# 25-CURRENT_MONITORING_DEVICES.net
KiCad netlist of a schematic drawn in Altium Designer
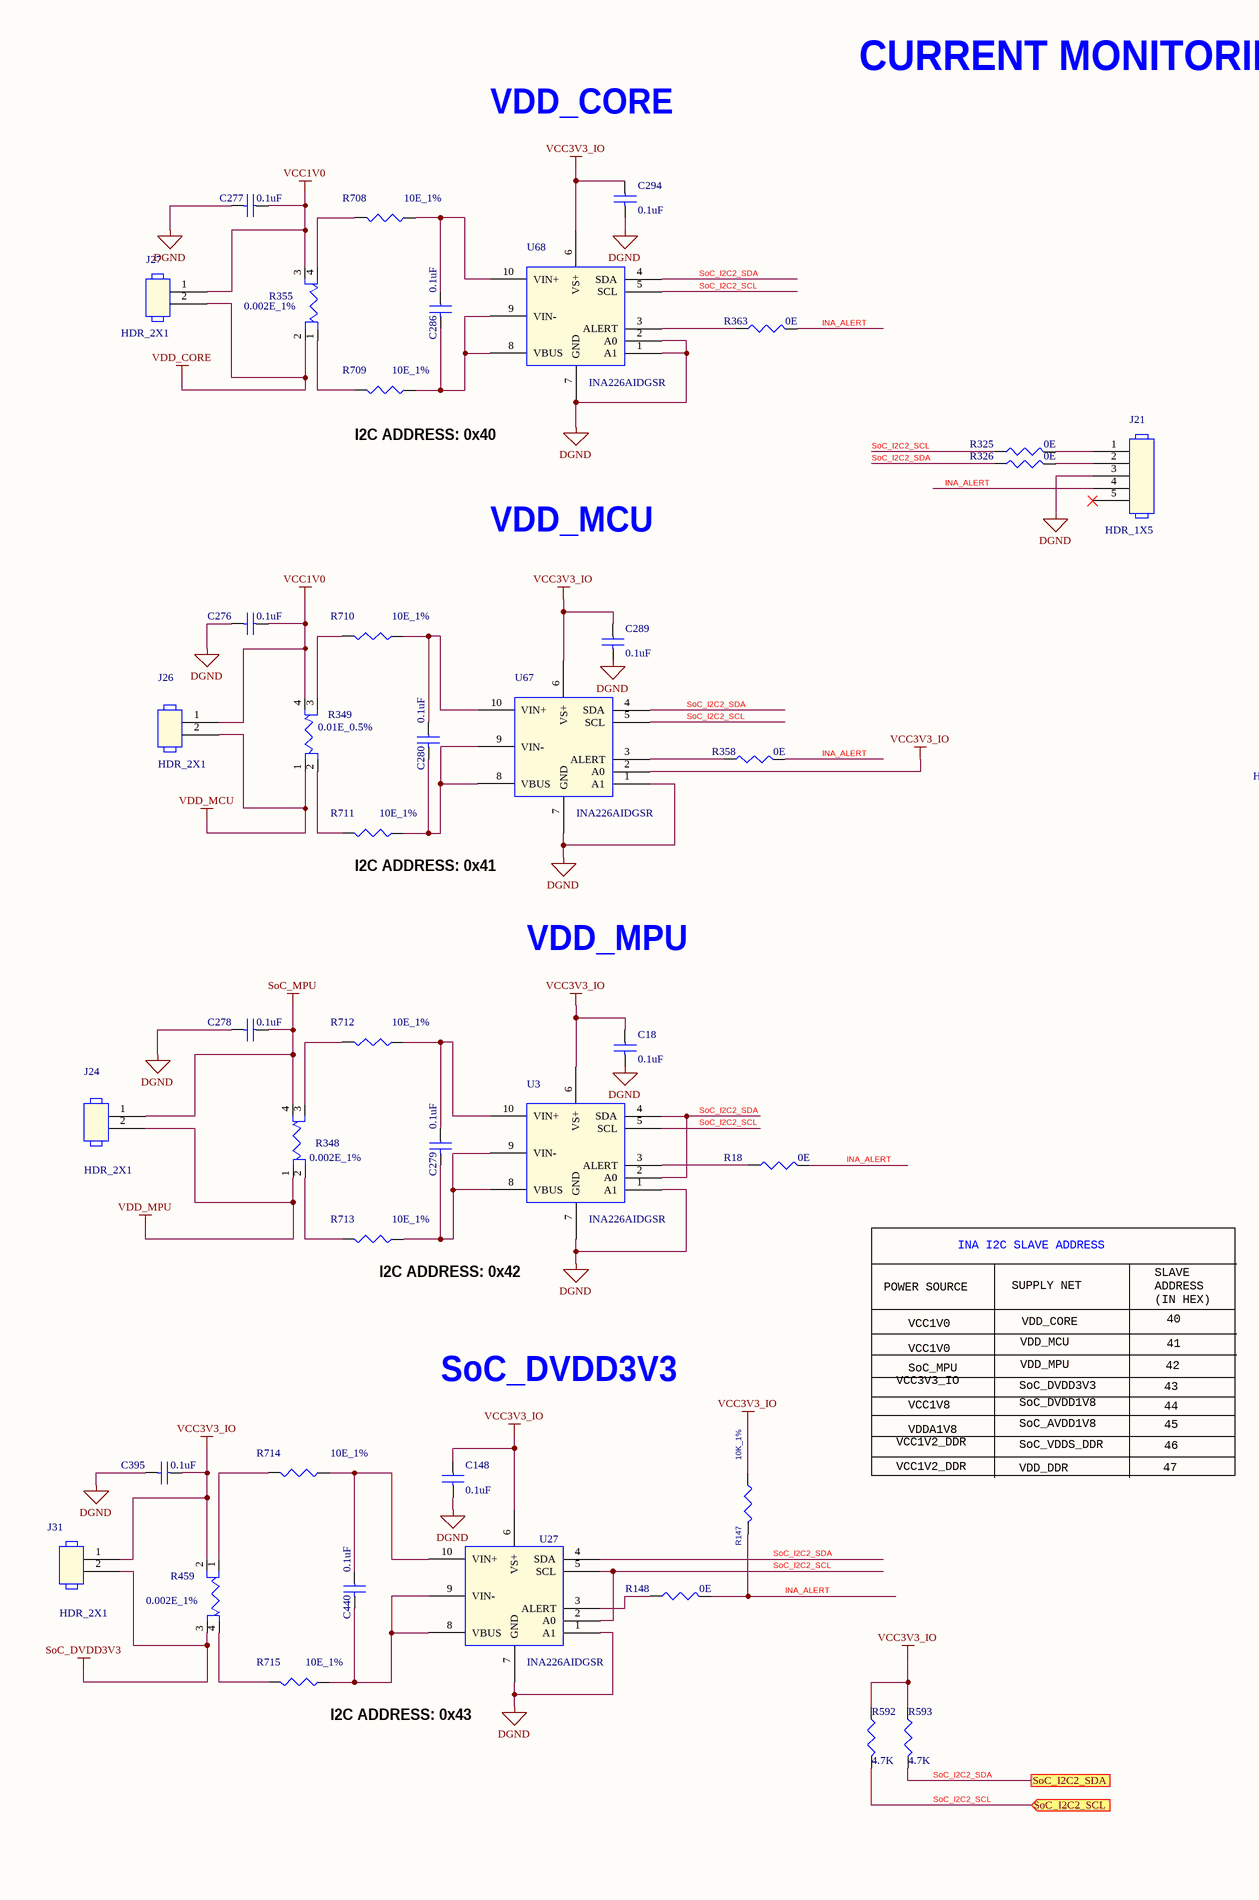
[diagram p0: 25-CURRENT MONITORING DEVICES.SchDoc, left]
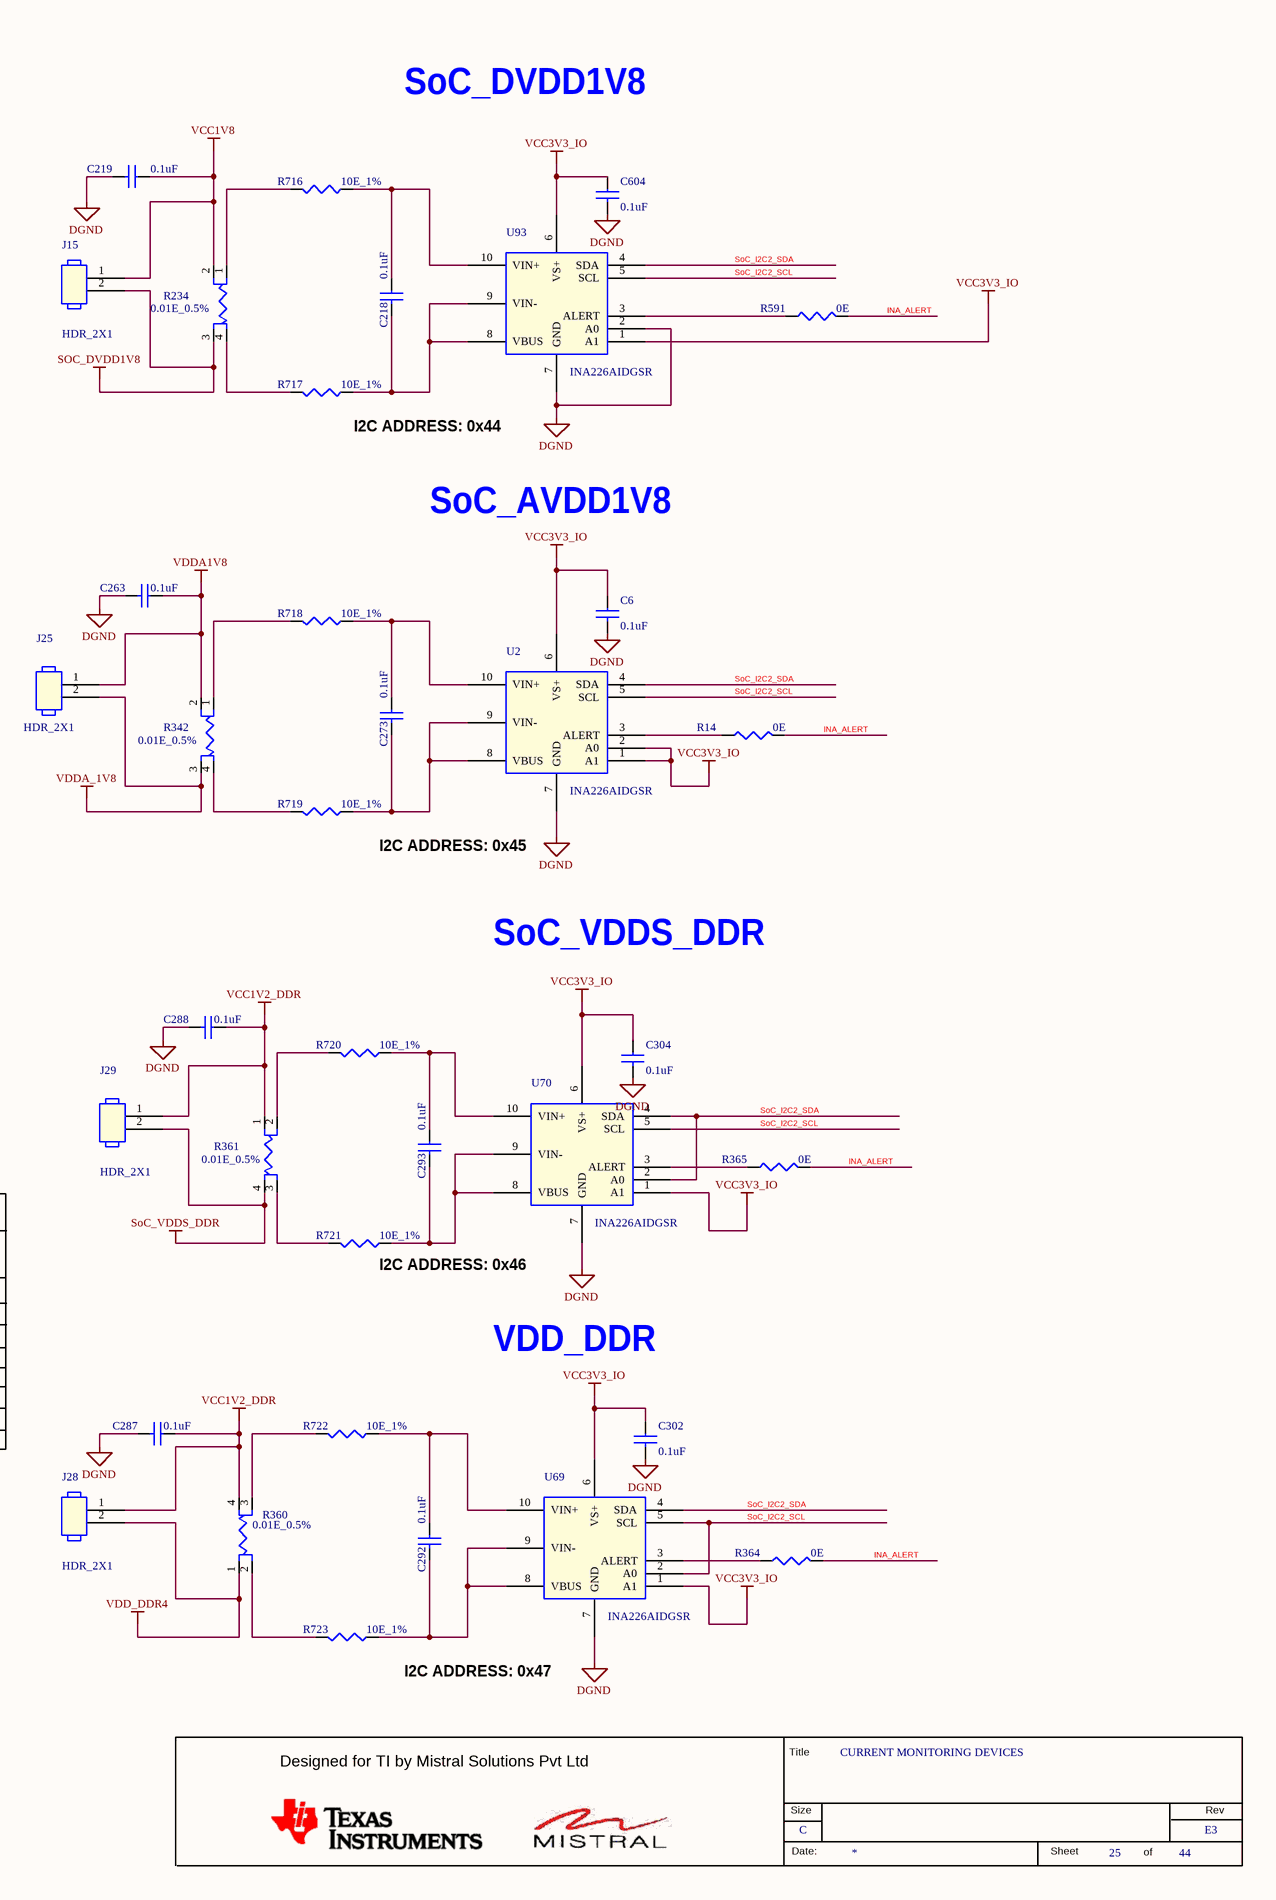
[diagram p1: 25-CURRENT MONITORING DEVICES.SchDoc, right]

(export (version "E")
  (design (tool "Eeschema 10.0.6"))
  (components
    (comp (ref "C6")
      (value "0.1uF")
      (footprint "CAP0201_0-5")
      (description "CAP CERAMIC 0.1uF 16V 10% X5R 0201")
      (fields (field (name "DISTRIBUTOR_PART_NUMBER") "490-16742-1-ND") (field (name "VOLTAGE") "16V"))
      (libsource (lib "*") (part "CAP_Dup5"))
    )
    (comp (ref "C18")
      (value "0.1uF")
      (footprint "CAP0201_0-5")
      (description "CAP CERAMIC 0.1uF 16V 10% X5R 0201")
      (fields
        (field (name "MISTRAL PART NO") "120009030072-R")
        (field (name "MFR_PART_NUMBER") "GRM033R61C104KE84J")
      )
      (libsource (lib "*") (part "CAP_Dup5"))
    )
    (comp (ref "C148")
      (value "0.1uF")
      (footprint "CAP0201_0-5")
      (description "CAP CERAMIC 0.1uF 16V 10% X5R 0201")
      (fields (field (name "DISTRIBUTOR_PART_NUMBER") "490-16742-1-ND") (field (name "VOLTAGE") "16V"))
      (libsource (lib "*") (part "CAP_Dup5"))
    )
    (comp (ref "C218")
      (value "0.1uF")
      (footprint "CAP0201_0-5")
      (description "CAP CERAMIC 0.1uF 16V 10% X5R 0201")
      (fields (field (name "PART_NUMBER") "EC01002") (field (name "MFR_PART_NUMBER") "GRM033R61C104KE84J"))
      (libsource (lib "*") (part "CAP_Dup2"))
    )
    (comp (ref "C219")
      (value "0.1uF")
      (footprint "CAP0201_0-5")
      (description "CAP CERAMIC 0.1uF 16V 10% X5R 0201")
      (fields (field (name "TASER_PART_NUMBER") "EC01002") (field (name "MISTRAL PART NO") "120009030072-R"))
      (libsource (lib "*") (part "CAP_Dup2"))
    )
    (comp (ref "C263")
      (value "0.1uF")
      (footprint "CAP0201_0-5")
      (description "CAP CERAMIC 0.1uF 16V 10% X5R 0201")
      (fields (field (name "PART_NUMBER") "EC01002") (field (name "MFR_PART_NUMBER") "GRM033R61C104KE84J"))
      (libsource (lib "*") (part "CAP_Dup2"))
    )
    (comp (ref "C273")
      (value "0.1uF")
      (footprint "CAP0201_0-5")
      (description "CAP CERAMIC 0.1uF 16V 10% X5R 0201")
      (fields (field (name "TASER_PART_NUMBER") "EC01002") (field (name "MISTRAL PART NO") "120009030072-R"))
      (libsource (lib "*") (part "CAP_Dup2"))
    )
    (comp (ref "C276")
      (value "0.1uF")
      (footprint "CAP0201_0-5")
      (description "CAP CERAMIC 0.1uF 16V 10% X5R 0201")
      (fields (field (name "PART_NUMBER") "EC01002") (field (name "MFR_PART_NUMBER") "GRM033R61C104KE84J"))
      (libsource (lib "*") (part "CAP_Dup2"))
    )
    (comp (ref "C277")
      (value "0.1uF")
      (footprint "CAP0201_0-5")
      (description "CAP CERAMIC 0.1uF 16V 10% X5R 0201")
      (fields (field (name "PART_NUMBER") "EC01002") (field (name "MFR_PART_NUMBER") "GRM033R61C104KE84J"))
      (libsource (lib "*") (part "CAP_Dup2"))
    )
    (comp (ref "C278")
      (value "0.1uF")
      (footprint "CAP0201_0-5")
      (description "CAP CERAMIC 0.1uF 16V 10% X5R 0201")
      (fields (field (name "PART_NUMBER") "EC01002") (field (name "MFR_PART_NUMBER") "GRM033R61C104KE84J"))
      (libsource (lib "*") (part "CAP_Dup2"))
    )
    (comp (ref "C279")
      (value "0.1uF")
      (footprint "CAP0201_0-5")
      (description "CAP CERAMIC 0.1uF 16V 10% X5R 0201")
      (fields (field (name "PART_NUMBER") "EC01002") (field (name "MFR_PART_NUMBER") "GRM033R61C104KE84J"))
      (libsource (lib "*") (part "CAP_Dup2"))
    )
    (comp (ref "C280")
      (value "0.1uF")
      (footprint "CAP0201_0-5")
      (description "CAP CERAMIC 0.1uF 16V 10% X5R 0201")
      (fields (field (name "PART_NUMBER") "EC01002") (field (name "MFR_PART_NUMBER") "GRM033R61C104KE84J"))
      (libsource (lib "*") (part "CAP_Dup2"))
    )
    (comp (ref "C286")
      (value "0.1uF")
      (footprint "CAP0201_0-5")
      (description "CAP CERAMIC 0.1uF 16V 10% X5R 0201")
      (fields (field (name "TASER_PART_NUMBER") "EC01002") (field (name "MISTRAL PART NO") "120009030072-R"))
      (libsource (lib "*") (part "CAP_Dup2"))
    )
    (comp (ref "C287")
      (value "0.1uF")
      (footprint "CAP0201_0-5")
      (description "CAP CERAMIC 0.1uF 16V 10% X5R 0201")
      (fields (field (name "TASER_PART_NUMBER") "EC01002") (field (name "MISTRAL PART NO") "120009030072-R"))
      (libsource (lib "*") (part "CAP_Dup2"))
    )
    (comp (ref "C288")
      (value "0.1uF")
      (footprint "CAP0201_0-5")
      (description "CAP CERAMIC 0.1uF 16V 10% X5R 0201")
      (fields (field (name "PART_NUMBER") "EC01002") (field (name "MFR_PART_NUMBER") "GRM033R61C104KE84J"))
      (libsource (lib "*") (part "CAP_Dup2"))
    )
    (comp (ref "C289")
      (value "0.1uF")
      (footprint "CAP0201_0-5")
      (description "CAP CERAMIC 0.1uF 16V 10% X5R 0201")
      (fields
        (field (name "MISTRAL PART NO") "120009030072-R")
        (field (name "MFR_PART_NUMBER") "GRM033R61C104KE84J")
      )
      (libsource (lib "*") (part "CAP_Dup5"))
    )
    (comp (ref "C292")
      (value "0.1uF")
      (footprint "CAP0201_0-5")
      (description "CAP CERAMIC 0.1uF 16V 10% X5R 0201")
      (fields (field (name "TASER_PART_NUMBER") "EC01002") (field (name "MISTRAL PART NO") "120009030072-R"))
      (libsource (lib "*") (part "CAP_Dup2"))
    )
    (comp (ref "C293")
      (value "0.1uF")
      (footprint "CAP0201_0-5")
      (description "CAP CERAMIC 0.1uF 16V 10% X5R 0201")
      (fields (field (name "TASER_PART_NUMBER") "EC01002") (field (name "MISTRAL PART NO") "120009030072-R"))
      (libsource (lib "*") (part "CAP_Dup2"))
    )
    (comp (ref "C294")
      (value "0.1uF")
      (footprint "CAP0201_0-5")
      (description "CAP CERAMIC 0.1uF 16V 10% X5R 0201")
      (fields
        (field (name "MISTRAL PART NO") "120009030072-R")
        (field (name "MFR_PART_NUMBER") "GRM033R61C104KE84J")
      )
      (libsource (lib "*") (part "CAP_Dup5"))
    )
    (comp (ref "C302")
      (value "0.1uF")
      (footprint "CAP0201_0-5")
      (description "CAP CERAMIC 0.1uF 16V 10% X5R 0201")
      (fields
        (field (name "MISTRAL PART NO") "120009030072-R")
        (field (name "MFR_PART_NUMBER") "GRM033R61C104KE84J")
      )
      (libsource (lib "*") (part "CAP_Dup5"))
    )
    (comp (ref "C304")
      (value "0.1uF")
      (footprint "CAP0201_0-5")
      (description "CAP CERAMIC 0.1uF 16V 10% X5R 0201")
      (fields (field (name "DISTRIBUTOR_PART_NUMBER") "490-16742-1-ND") (field (name "VOLTAGE") "16V"))
      (libsource (lib "*") (part "CAP_Dup5"))
    )
    (comp (ref "C395")
      (value "0.1uF")
      (footprint "CAP0201_0-5")
      (description "CAP CERAMIC 0.1uF 16V 10% X5R 0201")
      (fields (field (name "TASER_PART_NUMBER") "EC01002") (field (name "MISTRAL PART NO") "120009030072-R"))
      (libsource (lib "*") (part "CAP_Dup2"))
    )
    (comp (ref "C440")
      (value "0.1uF")
      (footprint "CAP0201_0-5")
      (description "CAP CERAMIC 0.1uF 16V 10% X5R 0201")
      (fields (field (name "TASER_PART_NUMBER") "EC01002") (field (name "MISTRAL PART NO") "120009030072-R"))
      (libsource (lib "*") (part "CAP_Dup2"))
    )
    (comp (ref "C604")
      (value "0.1uF")
      (footprint "CAP0201_0-5")
      (description "CAP CERAMIC 0.1uF 16V 10% X5R 0201")
      (fields
        (field (name "MISTRAL PART NO") "120009030072-R")
        (field (name "MFR_PART_NUMBER") "GRM033R61C104KE84J")
      )
      (libsource (lib "*") (part "CAP_Dup5"))
    )
    (comp (ref "J15")
      (value "HDR_2X1")
      (footprint "HDR_2X1_100_S_T_10-8")
      (description "CON HDR 2X1 2.54MM PITCH ST TH")
      (fields
        (field (name "DISTRIBUTOR_PART_NUMBER") "WM4000-ND")
        (field (name "MFR_PART_NUMBER") "22-03-2021")
      )
      (libsource (lib "*") (part "HEADER_2X1"))
    )
    (comp (ref "J21")
      (value "HDR_1X5")
      (footprint "HDR_5X1_100_S_T_11-2")
      (description "CON HDR 1X5 2.54MM PITCH ST TH")
      (fields (field (name "VOLTAGE") "NA") (field (name "MISTRAL PART NO") "150009030262-R"))
      (libsource (lib "*") (part "HEADER_5X1"))
    )
    (comp (ref "J24")
      (value "HDR_2X1")
      (footprint "HDR_2X1_100_S_T_10-8")
      (description "CON HDR 2X1 2.54MM PITCH ST TH")
      (fields
        (field (name "DISTRIBUTOR_PART_NUMBER") "WM4000-ND")
        (field (name "MFR_PART_NUMBER") "22-03-2021")
      )
      (libsource (lib "*") (part "HEADER_2X1"))
    )
    (comp (ref "J25")
      (value "HDR_2X1")
      (footprint "HDR_2X1_100_S_T_10-8")
      (description "CON HDR 2X1 2.54MM PITCH ST TH")
      (fields (field (name "VOLTAGE") "NA") (field (name "MISTRAL PART NO") "150009030246-R"))
      (libsource (lib "*") (part "HEADER_2X1"))
    )
    (comp (ref "J26")
      (value "HDR_2X1")
      (footprint "HDR_2X1_100_S_T_10-8")
      (description "CON HDR 2X1 2.54MM PITCH ST TH")
      (fields (field (name "VOLTAGE") "NA") (field (name "MISTRAL PART NO") "150009030246-R"))
      (libsource (lib "*") (part "HEADER_2X1"))
    )
    (comp (ref "J27")
      (value "HDR_2X1")
      (footprint "HDR_2X1_100_S_T_10-8")
      (description "CON HDR 2X1 2.54MM PITCH ST TH")
      (fields (field (name "VOLTAGE") "NA") (field (name "MISTRAL PART NO") "150009030246-R"))
      (libsource (lib "*") (part "HEADER_2X1"))
    )
    (comp (ref "J28")
      (value "HDR_2X1")
      (footprint "HDR_2X1_100_S_T_10-8")
      (description "CON HDR 2X1 2.54MM PITCH ST TH")
      (fields (field (name "VOLTAGE") "NA") (field (name "MISTRAL PART NO") "150009030246-R"))
      (libsource (lib "*") (part "HEADER_2X1"))
    )
    (comp (ref "J29")
      (value "HDR_2X1")
      (footprint "HDR_2X1_100_S_T_10-8")
      (description "CON HDR 2X1 2.54MM PITCH ST TH")
      (fields (field (name "VOLTAGE") "NA") (field (name "MISTRAL PART NO") "150009030246-R"))
      (libsource (lib "*") (part "HEADER_2X1"))
    )
    (comp (ref "J31")
      (value "HDR_2X1")
      (footprint "HDR_2X1_100_S_T_10-8")
      (description "CON HDR 2X1 2.54MM PITCH ST TH")
      (fields
        (field (name "DISTRIBUTOR_PART_NUMBER") "WM4000-ND")
        (field (name "MFR_PART_NUMBER") "22-03-2021")
      )
      (libsource (lib "*") (part "HEADER_2X1"))
    )
    (comp (ref "R14")
      (value "0E")
      (footprint "RES0402_0-5")
      (description "RES 0E 1/16W 0402")
      (fields (field (name "DISTRIBUTOR_PART_NUMBER") "541-0.0JCT-ND") (field (name "VOLTAGE") "NA"))
      (libsource (lib "*") (part "RESISTOR_Dup4"))
    )
    (comp (ref "R18")
      (value "0E")
      (footprint "RES0402_0-5")
      (description "RES 0E 1/16W 0402")
      (fields
        (field (name "MISTRAL PART NO") "110010080019-P")
        (field (name "MFR_PART_NUMBER") "CRCW04020000Z0ED")
      )
      (libsource (lib "*") (part "RESISTOR_Dup4"))
    )
    (comp (ref "R147")
      (value "10K_1%")
      (footprint "RES0402_0-5")
      (description "RES 10K 1/16W 1% 0402")
      (fields
        (field (name "MISTRAL PART NO") "110009030220-P")
        (field (name "MFR_PART_NUMBER") "RC0402FR-0710KL")
      )
      (libsource (lib "*") (part "RESISTOR_Dup2"))
    )
    (comp (ref "R148")
      (value "0E")
      (footprint "RES0402_0-5")
      (description "RES 0E 1/16W 0402")
      (fields
        (field (name "MISTRAL PART NO") "110010080019-P")
        (field (name "MFR_PART_NUMBER") "CRCW04020000Z0ED")
      )
      (libsource (lib "*") (part "RESISTOR_Dup4"))
    )
    (comp (ref "R234")
      (value "0.01E_0.5%")
      (footprint "RES1206-4TERM_0-75")
      (description "RES 0.01E 1/2W 0.5% 4-TERM1206")
      (fields (field (name "DISTRIBUTOR_PART_NUMBER") "LVK12R010DERCT-ND") (field (name "VOLTAGE") "NA"))
      (libsource (lib "*") (part "RESISTOR-4TERM"))
    )
    (comp (ref "R325")
      (value "0E")
      (footprint "RES0402_0-5")
      (description "RES 0E 1/16W 0402")
      (fields
        (field (name "MISTRAL PART NO") "110010080019-P")
        (field (name "MFR_PART_NUMBER") "CRCW04020000Z0ED")
      )
      (libsource (lib "*") (part "RESISTOR_Dup4"))
    )
    (comp (ref "R326")
      (value "0E")
      (footprint "RES0402_0-5")
      (description "RES 0E 1/16W 0402")
      (fields (field (name "DISTRIBUTOR_PART_NUMBER") "541-0.0JCT-ND") (field (name "VOLTAGE") "NA"))
      (libsource (lib "*") (part "RESISTOR_Dup4"))
    )
    (comp (ref "R342")
      (value "0.01E_0.5%")
      (footprint "RES1206-4TERM_0-75")
      (description "RES 0.01E 1/2W 0.5% 4-TERM1206")
      (fields (field (name "DISTRIBUTOR_PART_NUMBER") "LVK12R010DERCT-ND") (field (name "VOLTAGE") "NA"))
      (libsource (lib "*") (part "RESISTOR-4TERM"))
    )
    (comp (ref "R348")
      (value "0.002E_1%")
      (footprint "RES2512-4TERM_0-75")
      (description "RES 0.002E 2W 1% 4-TERM2512")
      (fields (field (name "DISTRIBUTOR_PART_NUMBER") "LVK25R002FERCT-ND") (field (name "VOLTAGE") "NA"))
      (libsource (lib "*") (part "RESISTOR-4TERM"))
    )
    (comp (ref "R349")
      (value "0.01E_0.5%")
      (footprint "RES1206-4TERM_0-75")
      (description "RES 0.01E 1/2W 0.5% 4-TERM1206")
      (fields (field (name "DISTRIBUTOR_PART_NUMBER") "LVK12R010DERCT-ND") (field (name "VOLTAGE") "NA"))
      (libsource (lib "*") (part "RESISTOR-4TERM"))
    )
    (comp (ref "R355")
      (value "0.002E_1%")
      (footprint "RES2512-4TERM_0-75")
      (description "RES 0.002E 2W 1% 4-TERM2512")
      (fields
        (field (name "MISTRAL PART NO") "110017090010-R")
        (field (name "MFR_PART_NUMBER") "LVK25R002FER")
      )
      (libsource (lib "*") (part "RESISTOR-4TERM"))
    )
    (comp (ref "R358")
      (value "0E")
      (footprint "RES0402_0-5")
      (description "RES 0E 1/16W 0402")
      (fields
        (field (name "MISTRAL PART NO") "110010080019-P")
        (field (name "MFR_PART_NUMBER") "CRCW04020000Z0ED")
      )
      (libsource (lib "*") (part "RESISTOR_Dup4"))
    )
    (comp (ref "R360")
      (value "0.01E_0.5%")
      (footprint "RES1206-4TERM_0-75")
      (description "RES 0.01E 1/2W 0.5% 4-TERM1206")
      (fields (field (name "DISTRIBUTOR_PART_NUMBER") "LVK12R010DERCT-ND") (field (name "VOLTAGE") "NA"))
      (libsource (lib "*") (part "RESISTOR-4TERM"))
    )
    (comp (ref "R361")
      (value "0.01E_0.5%")
      (footprint "RES1206-4TERM_0-75")
      (description "RES 0.01E 1/2W 0.5% 4-TERM1206")
      (fields
        (field (name "MISTRAL PART NO") "110017090009-R")
        (field (name "MFR_PART_NUMBER") "LVK12R010DER")
      )
      (libsource (lib "*") (part "RESISTOR-4TERM"))
    )
    (comp (ref "R363")
      (value "0E")
      (footprint "RES0402_0-5")
      (description "RES 0E 1/16W 0402")
      (fields
        (field (name "MISTRAL PART NO") "110010080019-P")
        (field (name "MFR_PART_NUMBER") "CRCW04020000Z0ED")
      )
      (libsource (lib "*") (part "RESISTOR_Dup4"))
    )
    (comp (ref "R364")
      (value "0E")
      (footprint "RES0402_0-5")
      (description "RES 0E 1/16W 0402")
      (fields (field (name "DISTRIBUTOR_PART_NUMBER") "541-0.0JCT-ND") (field (name "VOLTAGE") "NA"))
      (libsource (lib "*") (part "RESISTOR_Dup4"))
    )
    (comp (ref "R365")
      (value "0E")
      (footprint "RES0402_0-5")
      (description "RES 0E 1/16W 0402")
      (fields (field (name "DISTRIBUTOR_PART_NUMBER") "541-0.0JCT-ND") (field (name "VOLTAGE") "NA"))
      (libsource (lib "*") (part "RESISTOR_Dup4"))
    )
    (comp (ref "R459")
      (value "0.002E_1%")
      (footprint "RES2512-4TERM_0-75")
      (description "RES 0.002E 2W 1% 4-TERM2512")
      (fields
        (field (name "MISTRAL PART NO") "110017090010-R")
        (field (name "MFR_PART_NUMBER") "LVK25R002FER")
      )
      (libsource (lib "*") (part "RESISTOR-4TERM"))
    )
    (comp (ref "R591")
      (value "0E")
      (footprint "RES0402_0-5")
      (description "RES 0E 1/16W 0402")
      (fields (field (name "DISTRIBUTOR_PART_NUMBER") "541-0.0JCT-ND") (field (name "VOLTAGE") "NA"))
      (libsource (lib "*") (part "RESISTOR_Dup4"))
    )
    (comp (ref "R592")
      (value "4.7K")
      (footprint "RES0402")
      (description "RES 4.7K 1/16W 5% 0402")
      (fields (field (name "DISTRIBUTOR_PART_NUMBER") "311-4.7KJRCT-ND") (field (name "VOLTAGE") "NA"))
      (libsource (lib "*") (part "RESISTOR_Dup3"))
    )
    (comp (ref "R593")
      (value "4.7K")
      (footprint "RES0402")
      (description "RES 4.7K 1/16W 5% 0402")
      (fields (field (name "DISTRIBUTOR_PART_NUMBER") "311-4.7KJRCT-ND") (field (name "VOLTAGE") "NA"))
      (libsource (lib "*") (part "RESISTOR_Dup3"))
    )
    (comp (ref "R708")
      (value "10E_1%")
      (footprint "RES0402_0-5")
      (description "RES 10E 1/16W 1% 0402")
      (fields
        (field (name "MISTRAL PART NO") "110018020004-R")
        (field (name "MFR_PART_NUMBER") "RC0402FR-0710RL")
      )
      (libsource (lib "*") (part "RESISTOR_Dup5"))
    )
    (comp (ref "R709")
      (value "10E_1%")
      (footprint "RES0402_0-5")
      (description "RES 10E 1/16W 1% 0402")
      (fields (field (name "DISTRIBUTOR_PART_NUMBER") "311-10.0LRCT-ND") (field (name "VOLTAGE") "NA"))
      (libsource (lib "*") (part "RESISTOR_Dup5"))
    )
    (comp (ref "R710")
      (value "10E_1%")
      (footprint "RES0402_0-5")
      (description "RES 10E 1/16W 1% 0402")
      (fields (field (name "DISTRIBUTOR_PART_NUMBER") "311-10.0LRCT-ND") (field (name "VOLTAGE") "NA"))
      (libsource (lib "*") (part "RESISTOR_Dup5"))
    )
    (comp (ref "R711")
      (value "10E_1%")
      (footprint "RES0402_0-5")
      (description "RES 10E 1/16W 1% 0402")
      (fields
        (field (name "MISTRAL PART NO") "110018020004-R")
        (field (name "MFR_PART_NUMBER") "RC0402FR-0710RL")
      )
      (libsource (lib "*") (part "RESISTOR_Dup5"))
    )
    (comp (ref "R712")
      (value "10E_1%")
      (footprint "RES0402_0-5")
      (description "RES 10E 1/16W 1% 0402")
      (fields
        (field (name "MISTRAL PART NO") "110018020004-R")
        (field (name "MFR_PART_NUMBER") "RC0402FR-0710RL")
      )
      (libsource (lib "*") (part "RESISTOR_Dup5"))
    )
    (comp (ref "R713")
      (value "10E_1%")
      (footprint "RES0402_0-5")
      (description "RES 10E 1/16W 1% 0402")
      (fields
        (field (name "MISTRAL PART NO") "110018020004-R")
        (field (name "MFR_PART_NUMBER") "RC0402FR-0710RL")
      )
      (libsource (lib "*") (part "RESISTOR_Dup5"))
    )
    (comp (ref "R714")
      (value "10E_1%")
      (footprint "RES0402_0-5")
      (description "RES 10E 1/16W 1% 0402")
      (fields (field (name "DISTRIBUTOR_PART_NUMBER") "311-10.0LRCT-ND") (field (name "VOLTAGE") "NA"))
      (libsource (lib "*") (part "RESISTOR_Dup5"))
    )
    (comp (ref "R715")
      (value "10E_1%")
      (footprint "RES0402_0-5")
      (description "RES 10E 1/16W 1% 0402")
      (fields (field (name "DISTRIBUTOR_PART_NUMBER") "311-10.0LRCT-ND") (field (name "VOLTAGE") "NA"))
      (libsource (lib "*") (part "RESISTOR_Dup5"))
    )
    (comp (ref "R716")
      (value "10E_1%")
      (footprint "RES0402_0-5")
      (description "RES 10E 1/16W 1% 0402")
      (fields (field (name "DISTRIBUTOR_PART_NUMBER") "311-10.0LRCT-ND") (field (name "VOLTAGE") "NA"))
      (libsource (lib "*") (part "RESISTOR_Dup5"))
    )
    (comp (ref "R717")
      (value "10E_1%")
      (footprint "RES0402_0-5")
      (description "RES 10E 1/16W 1% 0402")
      (fields (field (name "DISTRIBUTOR_PART_NUMBER") "311-10.0LRCT-ND") (field (name "VOLTAGE") "NA"))
      (libsource (lib "*") (part "RESISTOR_Dup5"))
    )
    (comp (ref "R718")
      (value "10E_1%")
      (footprint "RES0402_0-5")
      (description "RES 10E 1/16W 1% 0402")
      (fields (field (name "DISTRIBUTOR_PART_NUMBER") "311-10.0LRCT-ND") (field (name "VOLTAGE") "NA"))
      (libsource (lib "*") (part "RESISTOR_Dup5"))
    )
    (comp (ref "R719")
      (value "10E_1%")
      (footprint "RES0402_0-5")
      (description "RES 10E 1/16W 1% 0402")
      (fields (field (name "DISTRIBUTOR_PART_NUMBER") "311-10.0LRCT-ND") (field (name "VOLTAGE") "NA"))
      (libsource (lib "*") (part "RESISTOR_Dup5"))
    )
    (comp (ref "R720")
      (value "10E_1%")
      (footprint "RES0402_0-5")
      (description "RES 10E 1/16W 1% 0402")
      (fields (field (name "DISTRIBUTOR_PART_NUMBER") "311-10.0LRCT-ND") (field (name "VOLTAGE") "NA"))
      (libsource (lib "*") (part "RESISTOR_Dup5"))
    )
    (comp (ref "R721")
      (value "10E_1%")
      (footprint "RES0402_0-5")
      (description "RES 10E 1/16W 1% 0402")
      (fields (field (name "DISTRIBUTOR_PART_NUMBER") "311-10.0LRCT-ND") (field (name "VOLTAGE") "NA"))
      (libsource (lib "*") (part "RESISTOR_Dup5"))
    )
    (comp (ref "R722")
      (value "10E_1%")
      (footprint "RES0402_0-5")
      (description "RES 10E 1/16W 1% 0402")
      (fields (field (name "DISTRIBUTOR_PART_NUMBER") "311-10.0LRCT-ND") (field (name "VOLTAGE") "NA"))
      (libsource (lib "*") (part "RESISTOR_Dup5"))
    )
    (comp (ref "R723")
      (value "10E_1%")
      (footprint "RES0402_0-5")
      (description "RES 10E 1/16W 1% 0402")
      (fields (field (name "DISTRIBUTOR_PART_NUMBER") "311-10.0LRCT-ND") (field (name "VOLTAGE") "NA"))
      (libsource (lib "*") (part "RESISTOR_Dup5"))
    )
    (comp (ref "U2")
      (value "INA226AIDGSR")
      (footprint "MSOP10_19-68_120X120_1-1")
      (description "IC BI-DIRECTIONAL CURRENT MONITER MSOP10")
      (fields
        (field (name "MISTRAL PART NO") "141011080019-R")
        (field (name "TOLERANCE") "NA")
        (field (name "LIBRARY PATH") "Y~{:}MIS_DATABAS~{E}Librar~{y}ALTIUM_TOO~{L}SCHEMATICS_PART~{S}MS_MISCINTERFACE_Library.schlib")
      )
      (libsource (lib "*") (part "INA226AIDGS_MSOP10"))
    )
    (comp (ref "U3")
      (value "INA226AIDGSR")
      (footprint "MSOP10_19-68_120X120_1-1")
      (description "IC BI-DIRECTIONAL CURRENT MONITER MSOP10")
      (fields
        (field (name "DISTRIBUTOR_PART_NUMBER") "296-29034-1-ND")
        (field (name "VOLTAGE") "NA")
        (field (name "LIBRARY PATH") "Y~{:}MIS_DATABAS~{E}Librar~{y}ALTIUM_TOO~{L}SCHEMATICS_PART~{S}MS_MISCINTERFACE_Library.schlib")
      )
      (libsource (lib "*") (part "INA226AIDGS_MSOP10"))
    )
    (comp (ref "U27")
      (value "INA226AIDGSR")
      (footprint "MSOP10_19-68_120X120_1-1")
      (description "IC BI-DIRECTIONAL CURRENT MONITER MSOP10")
      (fields
        (field (name "DISTRIBUTOR_PART_NUMBER") "296-29034-1-ND")
        (field (name "VOLTAGE") "NA")
        (field (name "LIBRARY PATH") "Y~{:}MIS_DATABAS~{E}Librar~{y}ALTIUM_TOO~{L}SCHEMATICS_PART~{S}MS_MISCINTERFACE_Library.schlib")
      )
      (libsource (lib "*") (part "INA226AIDGS_MSOP10"))
    )
    (comp (ref "U67")
      (value "INA226AIDGSR")
      (footprint "MSOP10_19-68_120X120_1-1")
      (description "IC BI-DIRECTIONAL CURRENT MONITER MSOP10")
      (fields
        (field (name "DISTRIBUTOR_PART_NUMBER") "296-29034-1-ND")
        (field (name "VOLTAGE") "NA")
        (field (name "LIBRARY PATH") "Y~{:}MIS_DATABAS~{E}Librar~{y}ALTIUM_TOO~{L}SCHEMATICS_PART~{S}MS_MISCINTERFACE_Library.schlib")
      )
      (libsource (lib "*") (part "INA226AIDGS_MSOP10"))
    )
    (comp (ref "U68")
      (value "INA226AIDGSR")
      (footprint "MSOP10_19-68_120X120_1-1")
      (description "IC BI-DIRECTIONAL CURRENT MONITER MSOP10")
      (fields
        (field (name "MISTRAL PART NO") "141011080019-R")
        (field (name "TOLERANCE") "NA")
        (field (name "LIBRARY PATH") "Y~{:}MIS_DATABAS~{E}Librar~{y}ALTIUM_TOO~{L}SCHEMATICS_PART~{S}MS_MISCINTERFACE_Library.schlib")
      )
      (libsource (lib "*") (part "INA226AIDGS_MSOP10"))
    )
    (comp (ref "U69")
      (value "INA226AIDGSR")
      (footprint "MSOP10_19-68_120X120_1-1")
      (description "IC BI-DIRECTIONAL CURRENT MONITER MSOP10")
      (fields
        (field (name "DISTRIBUTOR_PART_NUMBER") "296-29034-1-ND")
        (field (name "VOLTAGE") "NA")
        (field (name "LIBRARY PATH") "Y~{:}MIS_DATABAS~{E}Librar~{y}ALTIUM_TOO~{L}SCHEMATICS_PART~{S}MS_MISCINTERFACE_Library.schlib")
      )
      (libsource (lib "*") (part "INA226AIDGS_MSOP10"))
    )
    (comp (ref "U70")
      (value "INA226AIDGSR")
      (footprint "MSOP10_19-68_120X120_1-1")
      (description "IC BI-DIRECTIONAL CURRENT MONITER MSOP10")
      (fields
        (field (name "MISTRAL PART NO") "141011080019-R")
        (field (name "TOLERANCE") "NA")
        (field (name "LIBRARY PATH") "Y~{:}MIS_DATABAS~{E}Librar~{y}ALTIUM_TOO~{L}SCHEMATICS_PART~{S}MS_MISCINTERFACE_Library.schlib")
      )
      (libsource (lib "*") (part "INA226AIDGS_MSOP10"))
    )
    (comp (ref "U93")
      (value "INA226AIDGSR")
      (footprint "MSOP10_19-68_120X120_1-1")
      (description "IC BI-DIRECTIONAL CURRENT MONITER MSOP10")
      (fields
        (field (name "DISTRIBUTOR_PART_NUMBER") "296-29034-1-ND")
        (field (name "VOLTAGE") "NA")
        (field (name "LIBRARY PATH") "Y~{:}MIS_DATABAS~{E}Librar~{y}ALTIUM_TOO~{L}SCHEMATICS_PART~{S}MS_MISCINTERFACE_Library.schlib")
      )
      (libsource (lib "*") (part "INA226AIDGS_MSOP10"))
    )
  )
  (nets
    (net (code "1") (name "/INA_ALERT") (class "Default")
      (node (ref "J21") (pin "4") (pinfunction "4_4") (pintype "passive"))
      (node (ref "R14") (pin "2") (pinfunction "2_2") (pintype "passive"))
      (node (ref "R147") (pin "1") (pinfunction "1_1") (pintype "passive"))
      (node (ref "R148") (pin "2") (pinfunction "2_2") (pintype "passive"))
      (node (ref "R18") (pin "2") (pinfunction "2_2") (pintype "passive"))
      (node (ref "R358") (pin "2") (pinfunction "2_2") (pintype "passive"))
      (node (ref "R363") (pin "2") (pinfunction "2_2") (pintype "passive"))
      (node (ref "R364") (pin "2") (pinfunction "2_2") (pintype "passive"))
      (node (ref "R365") (pin "2") (pinfunction "2_2") (pintype "passive"))
      (node (ref "R591") (pin "2") (pinfunction "2_2") (pintype "passive"))
    )
    (net (code "2") (name "/SoC_I2C2_SCL") (class "Default")
      (node (ref "R325") (pin "1") (pinfunction "1_1") (pintype "passive"))
      (node (ref "R592") (pin "2") (pinfunction "2_2") (pintype "passive"))
      (node (ref "U2") (pin "5") (pinfunction "SCL_5") (pintype "passive"))
      (node (ref "U27") (pin "2") (pinfunction "A0_2") (pintype "passive"))
      (node (ref "U27") (pin "5") (pinfunction "SCL_5") (pintype "passive"))
      (node (ref "U3") (pin "5") (pinfunction "SCL_5") (pintype "passive"))
      (node (ref "U67") (pin "5") (pinfunction "SCL_5") (pintype "passive"))
      (node (ref "U68") (pin "5") (pinfunction "SCL_5") (pintype "passive"))
      (node (ref "U69") (pin "2") (pinfunction "A0_2") (pintype "passive"))
      (node (ref "U69") (pin "5") (pinfunction "SCL_5") (pintype "passive"))
      (node (ref "U70") (pin "5") (pinfunction "SCL_5") (pintype "passive"))
      (node (ref "U93") (pin "5") (pinfunction "SCL_5") (pintype "passive"))
    )
    (net (code "3") (name "/SoC_I2C2_SDA") (class "Default")
      (node (ref "R326") (pin "1") (pinfunction "1_1") (pintype "passive"))
      (node (ref "R593") (pin "2") (pinfunction "2_2") (pintype "passive"))
      (node (ref "U2") (pin "4") (pinfunction "SDA_4") (pintype "passive"))
      (node (ref "U27") (pin "4") (pinfunction "SDA_4") (pintype "passive"))
      (node (ref "U3") (pin "2") (pinfunction "A0_2") (pintype "passive"))
      (node (ref "U3") (pin "4") (pinfunction "SDA_4") (pintype "passive"))
      (node (ref "U67") (pin "4") (pinfunction "SDA_4") (pintype "passive"))
      (node (ref "U68") (pin "4") (pinfunction "SDA_4") (pintype "passive"))
      (node (ref "U69") (pin "4") (pinfunction "SDA_4") (pintype "passive"))
      (node (ref "U70") (pin "2") (pinfunction "A0_2") (pintype "passive"))
      (node (ref "U70") (pin "4") (pinfunction "SDA_4") (pintype "passive"))
      (node (ref "U93") (pin "4") (pinfunction "SDA_4") (pintype "passive"))
    )
    (net (code "4") (name "DGND") (class "Default")
      (node (ref "C148") (pin "2") (pinfunction "2_2") (pintype "passive"))
      (node (ref "C18") (pin "2") (pinfunction "2_2") (pintype "passive"))
      (node (ref "C219") (pin "2") (pinfunction "2_2") (pintype "passive"))
      (node (ref "C263") (pin "2") (pinfunction "2_2") (pintype "passive"))
      (node (ref "C276") (pin "2") (pinfunction "2_2") (pintype "passive"))
      (node (ref "C277") (pin "2") (pinfunction "2_2") (pintype "passive"))
      (node (ref "C278") (pin "2") (pinfunction "2_2") (pintype "passive"))
      (node (ref "C287") (pin "2") (pinfunction "2_2") (pintype "passive"))
      (node (ref "C288") (pin "2") (pinfunction "2_2") (pintype "passive"))
      (node (ref "C289") (pin "2") (pinfunction "2_2") (pintype "passive"))
      (node (ref "C294") (pin "2") (pinfunction "2_2") (pintype "passive"))
      (node (ref "C302") (pin "2") (pinfunction "2_2") (pintype "passive"))
      (node (ref "C304") (pin "2") (pinfunction "2_2") (pintype "passive"))
      (node (ref "C395") (pin "2") (pinfunction "2_2") (pintype "passive"))
      (node (ref "C6") (pin "2") (pinfunction "2_2") (pintype "passive"))
      (node (ref "C604") (pin "2") (pinfunction "2_2") (pintype "passive"))
      (node (ref "J21") (pin "3") (pinfunction "3_3") (pintype "passive"))
      (node (ref "U2") (pin "7") (pinfunction "GND_7") (pintype "power_in"))
      (node (ref "U27") (pin "1") (pinfunction "A1_1") (pintype "passive"))
      (node (ref "U27") (pin "7") (pinfunction "GND_7") (pintype "power_in"))
      (node (ref "U3") (pin "1") (pinfunction "A1_1") (pintype "passive"))
      (node (ref "U3") (pin "7") (pinfunction "GND_7") (pintype "power_in"))
      (node (ref "U67") (pin "1") (pinfunction "A1_1") (pintype "passive"))
      (node (ref "U67") (pin "7") (pinfunction "GND_7") (pintype "power_in"))
      (node (ref "U68") (pin "1") (pinfunction "A1_1") (pintype "passive"))
      (node (ref "U68") (pin "2") (pinfunction "A0_2") (pintype "passive"))
      (node (ref "U68") (pin "7") (pinfunction "GND_7") (pintype "power_in"))
      (node (ref "U69") (pin "7") (pinfunction "GND_7") (pintype "power_in"))
      (node (ref "U70") (pin "7") (pinfunction "GND_7") (pintype "power_in"))
      (node (ref "U93") (pin "2") (pinfunction "A0_2") (pintype "passive"))
      (node (ref "U93") (pin "7") (pinfunction "GND_7") (pintype "power_in"))
    )
    (net (code "5") (name "Net-(J21-Pad1)") (class "Default")
      (node (ref "J21") (pin "1") (pinfunction "1_1") (pintype "passive"))
      (node (ref "R325") (pin "2") (pinfunction "2_2") (pintype "passive"))
    )
    (net (code "6") (name "Net-(J21-Pad2)") (class "Default")
      (node (ref "J21") (pin "2") (pinfunction "2_2") (pintype "passive"))
      (node (ref "R326") (pin "2") (pinfunction "2_2") (pintype "passive"))
    )
    (net (code "7") (name "Net-(R234-Pad1)") (class "Default")
      (node (ref "R234") (pin "1") (pinfunction "1_1") (pintype "passive"))
      (node (ref "R716") (pin "2") (pinfunction "2_2") (pintype "passive"))
    )
    (net (code "8") (name "Net-(R234-Pad4)") (class "Default")
      (node (ref "R234") (pin "4") (pinfunction "4_4") (pintype "passive"))
      (node (ref "R717") (pin "2") (pinfunction "2_2") (pintype "passive"))
    )
    (net (code "9") (name "Net-(R342-Pad1)") (class "Default")
      (node (ref "R342") (pin "1") (pinfunction "1_1") (pintype "passive"))
      (node (ref "R718") (pin "2") (pinfunction "2_2") (pintype "passive"))
    )
    (net (code "10") (name "Net-(R342-Pad4)") (class "Default")
      (node (ref "R342") (pin "4") (pinfunction "4_4") (pintype "passive"))
      (node (ref "R719") (pin "2") (pinfunction "2_2") (pintype "passive"))
    )
    (net (code "11") (name "Net-(R348-Pad2)") (class "Default")
      (node (ref "R348") (pin "2") (pinfunction "2_2") (pintype "passive"))
      (node (ref "R713") (pin "2") (pinfunction "2_2") (pintype "passive"))
    )
    (net (code "12") (name "Net-(R348-Pad3)") (class "Default")
      (node (ref "R348") (pin "3") (pinfunction "3_3") (pintype "passive"))
      (node (ref "R712") (pin "2") (pinfunction "2_2") (pintype "passive"))
    )
    (net (code "13") (name "Net-(R349-Pad2)") (class "Default")
      (node (ref "R349") (pin "2") (pinfunction "2_2") (pintype "passive"))
      (node (ref "R711") (pin "2") (pinfunction "2_2") (pintype "passive"))
    )
    (net (code "14") (name "Net-(R349-Pad3)") (class "Default")
      (node (ref "R349") (pin "3") (pinfunction "3_3") (pintype "passive"))
      (node (ref "R710") (pin "2") (pinfunction "2_2") (pintype "passive"))
    )
    (net (code "15") (name "Net-(R355-Pad1)") (class "Default")
      (node (ref "R355") (pin "1") (pinfunction "1_1") (pintype "passive"))
      (node (ref "R709") (pin "2") (pinfunction "2_2") (pintype "passive"))
    )
    (net (code "16") (name "Net-(R355-Pad4)") (class "Default")
      (node (ref "R355") (pin "4") (pinfunction "4_4") (pintype "passive"))
      (node (ref "R708") (pin "2") (pinfunction "2_2") (pintype "passive"))
    )
    (net (code "17") (name "Net-(R360-Pad2)") (class "Default")
      (node (ref "R360") (pin "2") (pinfunction "2_2") (pintype "passive"))
      (node (ref "R723") (pin "2") (pinfunction "2_2") (pintype "passive"))
    )
    (net (code "18") (name "Net-(R360-Pad3)") (class "Default")
      (node (ref "R360") (pin "3") (pinfunction "3_3") (pintype "passive"))
      (node (ref "R722") (pin "2") (pinfunction "2_2") (pintype "passive"))
    )
    (net (code "19") (name "Net-(R361-Pad2)") (class "Default")
      (node (ref "R361") (pin "2") (pinfunction "2_2") (pintype "passive"))
      (node (ref "R720") (pin "2") (pinfunction "2_2") (pintype "passive"))
    )
    (net (code "20") (name "Net-(R361-Pad3)") (class "Default")
      (node (ref "R361") (pin "3") (pinfunction "3_3") (pintype "passive"))
      (node (ref "R721") (pin "2") (pinfunction "2_2") (pintype "passive"))
    )
    (net (code "21") (name "Net-(R459-Pad1)") (class "Default")
      (node (ref "R459") (pin "1") (pinfunction "1_1") (pintype "passive"))
      (node (ref "R714") (pin "2") (pinfunction "2_2") (pintype "passive"))
    )
    (net (code "22") (name "Net-(R459-Pad4)") (class "Default")
      (node (ref "R459") (pin "4") (pinfunction "4_4") (pintype "passive"))
      (node (ref "R715") (pin "2") (pinfunction "2_2") (pintype "passive"))
    )
    (net (code "23") (name "Net-(U2-ALERT)") (class "Default")
      (node (ref "R14") (pin "1") (pinfunction "1_1") (pintype "passive"))
      (node (ref "U2") (pin "3") (pinfunction "ALERT_3") (pintype "passive"))
    )
    (net (code "24") (name "Net-(U2-VBUS)") (class "Default")
      (node (ref "C273") (pin "2") (pinfunction "2_2") (pintype "passive"))
      (node (ref "R719") (pin "1") (pinfunction "1_1") (pintype "passive"))
      (node (ref "U2") (pin "8") (pinfunction "VBUS_8") (pintype "passive"))
      (node (ref "U2") (pin "9") (pinfunction "VIN-_9") (pintype "passive"))
    )
    (net (code "25") (name "Net-(U2-VIN+)") (class "Default")
      (node (ref "C273") (pin "1") (pinfunction "1_1") (pintype "passive"))
      (node (ref "R718") (pin "1") (pinfunction "1_1") (pintype "passive"))
      (node (ref "U2") (pin "10") (pinfunction "VIN+_10") (pintype "passive"))
    )
    (net (code "26") (name "Net-(U3-ALERT)") (class "Default")
      (node (ref "R18") (pin "1") (pinfunction "1_1") (pintype "passive"))
      (node (ref "U3") (pin "3") (pinfunction "ALERT_3") (pintype "passive"))
    )
    (net (code "27") (name "Net-(U3-VBUS)") (class "Default")
      (node (ref "C279") (pin "2") (pinfunction "2_2") (pintype "passive"))
      (node (ref "R713") (pin "1") (pinfunction "1_1") (pintype "passive"))
      (node (ref "U3") (pin "8") (pinfunction "VBUS_8") (pintype "passive"))
      (node (ref "U3") (pin "9") (pinfunction "VIN-_9") (pintype "passive"))
    )
    (net (code "28") (name "Net-(U3-VIN+)") (class "Default")
      (node (ref "C279") (pin "1") (pinfunction "1_1") (pintype "passive"))
      (node (ref "R712") (pin "1") (pinfunction "1_1") (pintype "passive"))
      (node (ref "U3") (pin "10") (pinfunction "VIN+_10") (pintype "passive"))
    )
    (net (code "29") (name "Net-(U27-ALERT)") (class "Default")
      (node (ref "R148") (pin "1") (pinfunction "1_1") (pintype "passive"))
      (node (ref "U27") (pin "3") (pinfunction "ALERT_3") (pintype "passive"))
    )
    (net (code "30") (name "Net-(U27-VBUS)") (class "Default")
      (node (ref "C440") (pin "2") (pinfunction "2_2") (pintype "passive"))
      (node (ref "R715") (pin "1") (pinfunction "1_1") (pintype "passive"))
      (node (ref "U27") (pin "8") (pinfunction "VBUS_8") (pintype "passive"))
      (node (ref "U27") (pin "9") (pinfunction "VIN-_9") (pintype "passive"))
    )
    (net (code "31") (name "Net-(U27-VIN+)") (class "Default")
      (node (ref "C440") (pin "1") (pinfunction "1_1") (pintype "passive"))
      (node (ref "R714") (pin "1") (pinfunction "1_1") (pintype "passive"))
      (node (ref "U27") (pin "10") (pinfunction "VIN+_10") (pintype "passive"))
    )
    (net (code "32") (name "Net-(U67-ALERT)") (class "Default")
      (node (ref "R358") (pin "1") (pinfunction "1_1") (pintype "passive"))
      (node (ref "U67") (pin "3") (pinfunction "ALERT_3") (pintype "passive"))
    )
    (net (code "33") (name "Net-(U67-VBUS)") (class "Default")
      (node (ref "C280") (pin "2") (pinfunction "2_2") (pintype "passive"))
      (node (ref "R711") (pin "1") (pinfunction "1_1") (pintype "passive"))
      (node (ref "U67") (pin "8") (pinfunction "VBUS_8") (pintype "passive"))
      (node (ref "U67") (pin "9") (pinfunction "VIN-_9") (pintype "passive"))
    )
    (net (code "34") (name "Net-(U67-VIN+)") (class "Default")
      (node (ref "C280") (pin "1") (pinfunction "1_1") (pintype "passive"))
      (node (ref "R710") (pin "1") (pinfunction "1_1") (pintype "passive"))
      (node (ref "U67") (pin "10") (pinfunction "VIN+_10") (pintype "passive"))
    )
    (net (code "35") (name "Net-(U68-ALERT)") (class "Default")
      (node (ref "R363") (pin "1") (pinfunction "1_1") (pintype "passive"))
      (node (ref "U68") (pin "3") (pinfunction "ALERT_3") (pintype "passive"))
    )
    (net (code "36") (name "Net-(U68-VBUS)") (class "Default")
      (node (ref "C286") (pin "2") (pinfunction "2_2") (pintype "passive"))
      (node (ref "R709") (pin "1") (pinfunction "1_1") (pintype "passive"))
      (node (ref "U68") (pin "8") (pinfunction "VBUS_8") (pintype "passive"))
      (node (ref "U68") (pin "9") (pinfunction "VIN-_9") (pintype "passive"))
    )
    (net (code "37") (name "Net-(U68-VIN+)") (class "Default")
      (node (ref "C286") (pin "1") (pinfunction "1_1") (pintype "passive"))
      (node (ref "R708") (pin "1") (pinfunction "1_1") (pintype "passive"))
      (node (ref "U68") (pin "10") (pinfunction "VIN+_10") (pintype "passive"))
    )
    (net (code "38") (name "Net-(U69-ALERT)") (class "Default")
      (node (ref "R364") (pin "1") (pinfunction "1_1") (pintype "passive"))
      (node (ref "U69") (pin "3") (pinfunction "ALERT_3") (pintype "passive"))
    )
    (net (code "39") (name "Net-(U69-VBUS)") (class "Default")
      (node (ref "C292") (pin "2") (pinfunction "2_2") (pintype "passive"))
      (node (ref "R723") (pin "1") (pinfunction "1_1") (pintype "passive"))
      (node (ref "U69") (pin "8") (pinfunction "VBUS_8") (pintype "passive"))
      (node (ref "U69") (pin "9") (pinfunction "VIN-_9") (pintype "passive"))
    )
    (net (code "40") (name "Net-(U69-VIN+)") (class "Default")
      (node (ref "C292") (pin "1") (pinfunction "1_1") (pintype "passive"))
      (node (ref "R722") (pin "1") (pinfunction "1_1") (pintype "passive"))
      (node (ref "U69") (pin "10") (pinfunction "VIN+_10") (pintype "passive"))
    )
    (net (code "41") (name "Net-(U70-ALERT)") (class "Default")
      (node (ref "R365") (pin "1") (pinfunction "1_1") (pintype "passive"))
      (node (ref "U70") (pin "3") (pinfunction "ALERT_3") (pintype "passive"))
    )
    (net (code "42") (name "Net-(U70-VBUS)") (class "Default")
      (node (ref "C293") (pin "2") (pinfunction "2_2") (pintype "passive"))
      (node (ref "R721") (pin "1") (pinfunction "1_1") (pintype "passive"))
      (node (ref "U70") (pin "8") (pinfunction "VBUS_8") (pintype "passive"))
      (node (ref "U70") (pin "9") (pinfunction "VIN-_9") (pintype "passive"))
    )
    (net (code "43") (name "Net-(U70-VIN+)") (class "Default")
      (node (ref "C293") (pin "1") (pinfunction "1_1") (pintype "passive"))
      (node (ref "R720") (pin "1") (pinfunction "1_1") (pintype "passive"))
      (node (ref "U70") (pin "10") (pinfunction "VIN+_10") (pintype "passive"))
    )
    (net (code "44") (name "Net-(U93-ALERT)") (class "Default")
      (node (ref "R591") (pin "1") (pinfunction "1_1") (pintype "passive"))
      (node (ref "U93") (pin "3") (pinfunction "ALERT_3") (pintype "passive"))
    )
    (net (code "45") (name "Net-(U93-VBUS)") (class "Default")
      (node (ref "C218") (pin "2") (pinfunction "2_2") (pintype "passive"))
      (node (ref "R717") (pin "1") (pinfunction "1_1") (pintype "passive"))
      (node (ref "U93") (pin "8") (pinfunction "VBUS_8") (pintype "passive"))
      (node (ref "U93") (pin "9") (pinfunction "VIN-_9") (pintype "passive"))
    )
    (net (code "46") (name "Net-(U93-VIN+)") (class "Default")
      (node (ref "C218") (pin "1") (pinfunction "1_1") (pintype "passive"))
      (node (ref "R716") (pin "1") (pinfunction "1_1") (pintype "passive"))
      (node (ref "U93") (pin "10") (pinfunction "VIN+_10") (pintype "passive"))
    )
    (net (code "47") (name "SOC_DVDD1V8") (class "Default")
      (node (ref "J15") (pin "2") (pinfunction "2_2") (pintype "passive"))
      (node (ref "R234") (pin "3") (pinfunction "3_3") (pintype "passive"))
    )
    (net (code "48") (name "SoC_DVDD3V3") (class "Default")
      (node (ref "J31") (pin "2") (pinfunction "2_2") (pintype "passive"))
      (node (ref "R459") (pin "3") (pinfunction "3_3") (pintype "passive"))
    )
    (net (code "49") (name "SoC_MPU") (class "Default")
      (node (ref "C278") (pin "1") (pinfunction "1_1") (pintype "passive"))
      (node (ref "J24") (pin "1") (pinfunction "1_1") (pintype "passive"))
      (node (ref "R348") (pin "4") (pinfunction "4_4") (pintype "passive"))
    )
    (net (code "50") (name "SoC_VDDS_DDR") (class "Default")
      (node (ref "J29") (pin "2") (pinfunction "2_2") (pintype "passive"))
      (node (ref "R361") (pin "4") (pinfunction "4_4") (pintype "passive"))
    )
    (net (code "51") (name "VCC1V0") (class "Default")
      (node (ref "C276") (pin "1") (pinfunction "1_1") (pintype "passive"))
      (node (ref "C277") (pin "1") (pinfunction "1_1") (pintype "passive"))
      (node (ref "J26") (pin "1") (pinfunction "1_1") (pintype "passive"))
      (node (ref "J27") (pin "1") (pinfunction "1_1") (pintype "passive"))
      (node (ref "R349") (pin "4") (pinfunction "4_4") (pintype "passive"))
      (node (ref "R355") (pin "3") (pinfunction "3_3") (pintype "passive"))
    )
    (net (code "52") (name "VCC1V2_DDR") (class "Default")
      (node (ref "C287") (pin "1") (pinfunction "1_1") (pintype "passive"))
      (node (ref "C288") (pin "1") (pinfunction "1_1") (pintype "passive"))
      (node (ref "J28") (pin "1") (pinfunction "1_1") (pintype "passive"))
      (node (ref "J29") (pin "1") (pinfunction "1_1") (pintype "passive"))
      (node (ref "R360") (pin "4") (pinfunction "4_4") (pintype "passive"))
      (node (ref "R361") (pin "1") (pinfunction "1_1") (pintype "passive"))
    )
    (net (code "53") (name "VCC1V8") (class "Default")
      (node (ref "C219") (pin "1") (pinfunction "1_1") (pintype "passive"))
      (node (ref "J15") (pin "1") (pinfunction "1_1") (pintype "passive"))
      (node (ref "R234") (pin "2") (pinfunction "2_2") (pintype "passive"))
    )
    (net (code "54") (name "VCC3V3_IO") (class "Default")
      (node (ref "C148") (pin "1") (pinfunction "1_1") (pintype "passive"))
      (node (ref "C18") (pin "1") (pinfunction "1_1") (pintype "passive"))
      (node (ref "C289") (pin "1") (pinfunction "1_1") (pintype "passive"))
      (node (ref "C294") (pin "1") (pinfunction "1_1") (pintype "passive"))
      (node (ref "C302") (pin "1") (pinfunction "1_1") (pintype "passive"))
      (node (ref "C304") (pin "1") (pinfunction "1_1") (pintype "passive"))
      (node (ref "C395") (pin "1") (pinfunction "1_1") (pintype "passive"))
      (node (ref "C6") (pin "1") (pinfunction "1_1") (pintype "passive"))
      (node (ref "C604") (pin "1") (pinfunction "1_1") (pintype "passive"))
      (node (ref "J31") (pin "1") (pinfunction "1_1") (pintype "passive"))
      (node (ref "R147") (pin "2") (pinfunction "2_2") (pintype "passive"))
      (node (ref "R459") (pin "2") (pinfunction "2_2") (pintype "passive"))
      (node (ref "R592") (pin "1") (pinfunction "1_1") (pintype "passive"))
      (node (ref "R593") (pin "1") (pinfunction "1_1") (pintype "passive"))
      (node (ref "U2") (pin "1") (pinfunction "A1_1") (pintype "passive"))
      (node (ref "U2") (pin "2") (pinfunction "A0_2") (pintype "passive"))
      (node (ref "U2") (pin "6") (pinfunction "VS+_6") (pintype "power_in"))
      (node (ref "U27") (pin "6") (pinfunction "VS+_6") (pintype "power_in"))
      (node (ref "U3") (pin "6") (pinfunction "VS+_6") (pintype "power_in"))
      (node (ref "U67") (pin "2") (pinfunction "A0_2") (pintype "passive"))
      (node (ref "U67") (pin "6") (pinfunction "VS+_6") (pintype "power_in"))
      (node (ref "U68") (pin "6") (pinfunction "VS+_6") (pintype "power_in"))
      (node (ref "U69") (pin "1") (pinfunction "A1_1") (pintype "passive"))
      (node (ref "U69") (pin "6") (pinfunction "VS+_6") (pintype "power_in"))
      (node (ref "U70") (pin "1") (pinfunction "A1_1") (pintype "passive"))
      (node (ref "U70") (pin "6") (pinfunction "VS+_6") (pintype "power_in"))
      (node (ref "U93") (pin "1") (pinfunction "A1_1") (pintype "passive"))
      (node (ref "U93") (pin "6") (pinfunction "VS+_6") (pintype "power_in"))
    )
    (net (code "55") (name "VDDA1V8") (class "Default")
      (node (ref "C263") (pin "1") (pinfunction "1_1") (pintype "passive"))
      (node (ref "J25") (pin "1") (pinfunction "1_1") (pintype "passive"))
      (node (ref "R342") (pin "2") (pinfunction "2_2") (pintype "passive"))
    )
    (net (code "56") (name "VDDA_1V8") (class "Default")
      (node (ref "J25") (pin "2") (pinfunction "2_2") (pintype "passive"))
      (node (ref "R342") (pin "3") (pinfunction "3_3") (pintype "passive"))
    )
    (net (code "57") (name "VDD_CORE") (class "Default")
      (node (ref "J27") (pin "2") (pinfunction "2_2") (pintype "passive"))
      (node (ref "R355") (pin "2") (pinfunction "2_2") (pintype "passive"))
    )
    (net (code "58") (name "VDD_DDR4") (class "Default")
      (node (ref "J28") (pin "2") (pinfunction "2_2") (pintype "passive"))
      (node (ref "R360") (pin "1") (pinfunction "1_1") (pintype "passive"))
    )
    (net (code "59") (name "VDD_MCU") (class "Default")
      (node (ref "J26") (pin "2") (pinfunction "2_2") (pintype "passive"))
      (node (ref "R349") (pin "1") (pinfunction "1_1") (pintype "passive"))
    )
    (net (code "60") (name "VDD_MPU") (class "Default")
      (node (ref "J24") (pin "2") (pinfunction "2_2") (pintype "passive"))
      (node (ref "R348") (pin "1") (pinfunction "1_1") (pintype "passive"))
    )
    (net (code "61") (name "unconnected-(J21-Pad5)") (class "Default")
      (node (ref "J21") (pin "5") (pinfunction "5_5") (pintype "passive+no_connect"))
    )
  )
)
